# oshpark2_1_2-peripherals.net
KiCad netlist of a schematic drawn in EAGLE
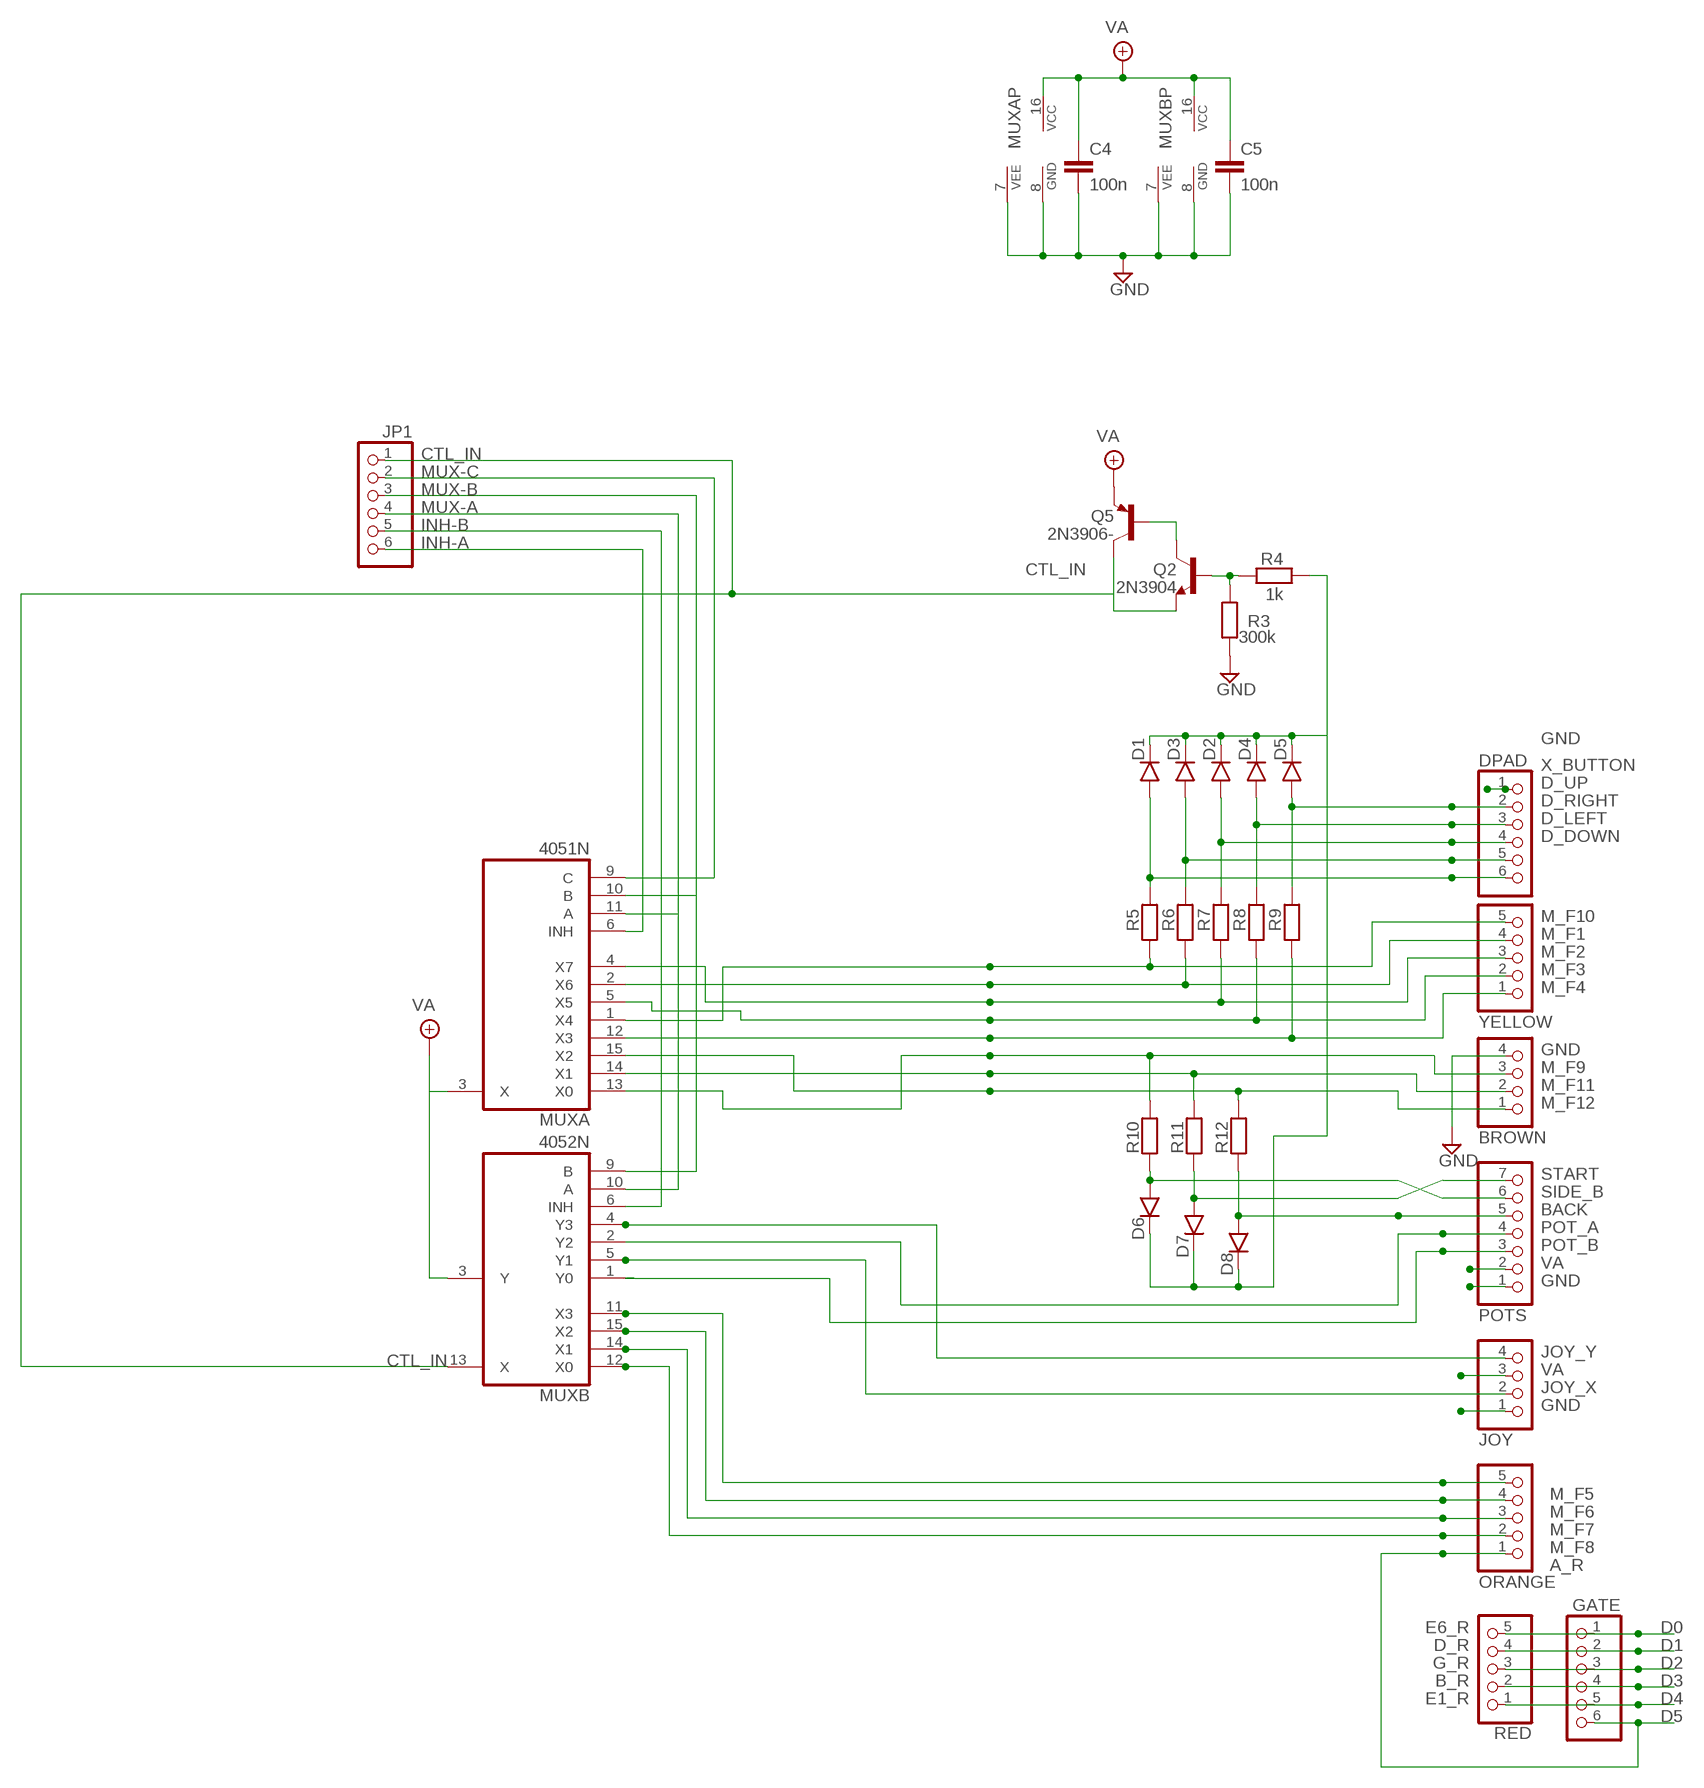
[diagram p0: schematic, sheet 1]

(export (version "E")
  (design (tool "Eeschema 10.0.6"))
  (components
    (comp (ref "BROWN")
      (value "PINHD-1X4")
      (footprint "eagle-import:1X04")
      (libsource (lib "eagle-import") (part "PINHD-1X4"))
    )
    (comp (ref "C4")
      (value "100n")
      (footprint "eagle-import:050X030_050_1")
      (libsource (lib "eagle-import") (part "050X030_0501"))
    )
    (comp (ref "C5")
      (value "100n")
      (footprint "eagle-import:050X030_050_3")
      (libsource (lib "eagle-import") (part "050X030_050"))
    )
    (comp (ref "D1")
      (value "1N4148-2")
      (footprint "eagle-import:DO35-2")
      (libsource (lib "eagle-import") (part "1N4148-2"))
    )
    (comp (ref "D2")
      (value "1N4148-2")
      (footprint "eagle-import:DO35-2")
      (libsource (lib "eagle-import") (part "1N4148-2"))
    )
    (comp (ref "D3")
      (value "1N4148-2")
      (footprint "eagle-import:DO35-2")
      (libsource (lib "eagle-import") (part "1N4148-2"))
    )
    (comp (ref "D4")
      (value "1N4148-2")
      (footprint "eagle-import:DO35-2")
      (libsource (lib "eagle-import") (part "1N4148-2"))
    )
    (comp (ref "D5")
      (value "1N4148-2")
      (footprint "eagle-import:DO35-2")
      (libsource (lib "eagle-import") (part "1N4148-2"))
    )
    (comp (ref "D6")
      (value "1N4148-2")
      (footprint "eagle-import:DO35-2")
      (libsource (lib "eagle-import") (part "1N4148-2"))
    )
    (comp (ref "D7")
      (value "1N4148-2")
      (footprint "eagle-import:DO35-2")
      (libsource (lib "eagle-import") (part "1N4148-2"))
    )
    (comp (ref "D8")
      (value "1N4148-2")
      (footprint "eagle-import:DO35-2")
      (libsource (lib "eagle-import") (part "1N4148-2"))
    )
    (comp (ref "DPAD")
      (value "PINHD-1X6")
      (footprint "eagle-import:1X06")
      (libsource (lib "eagle-import") (part "PINHD-1X6"))
    )
    (comp (ref "GATE")
      (value "PINHD-1X6")
      (footprint "eagle-import:1X06")
      (libsource (lib "eagle-import") (part "PINHD-1X6"))
    )
    (comp (ref "JOY")
      (value "PINHD-1X4")
      (footprint "eagle-import:1X04")
      (libsource (lib "eagle-import") (part "PINHD-1X4"))
    )
    (comp (ref "JP1")
      (value "PINHD-1X6")
      (footprint "eagle-import:1X06")
      (libsource (lib "eagle-import") (part "PINHD-1X6"))
    )
    (comp (ref "MUXA")
      (value "4051N")
      (footprint "eagle-import:DIL16")
      (libsource (lib "eagle-import") (part "4051N"))
    )
    (comp (ref "MUXB")
      (value "4052N")
      (footprint "eagle-import:DIL16")
      (libsource (lib "eagle-import") (part "4052N"))
    )
    (comp (ref "ORANGE")
      (value "PINHD-1X5")
      (footprint "eagle-import:1X05")
      (libsource (lib "eagle-import") (part "PINHD-1X5"))
    )
    (comp (ref "POTS")
      (value "PINHD-1X7")
      (footprint "eagle-import:1X07")
      (libsource (lib "eagle-import") (part "PINHD-1X7"))
    )
    (comp (ref "Q2")
      (value "2N3904")
      (footprint "eagle-import:TO92-")
      (libsource (lib "eagle-import") (part "2N3904"))
    )
    (comp (ref "Q5")
      (value "2N3906-")
      (footprint "eagle-import:TO92-")
      (libsource (lib "eagle-import") (part "2N3906-"))
    )
    (comp (ref "R3")
      (value "300k")
      (footprint "eagle-import:R0207_1V")
      (libsource (lib "eagle-import") (part "6MM-EU1"))
    )
    (comp (ref "R4")
      (value "1k")
      (footprint "eagle-import:R0207_3")
      (libsource (lib "eagle-import") (part "6MM-EU"))
    )
    (comp (ref "R5")
      (value "30k")
      (footprint "eagle-import:R0207_1V")
      (libsource (lib "eagle-import") (part "6MM-EU1"))
    )
    (comp (ref "R6")
      (value "30k")
      (footprint "eagle-import:R0207_1V")
      (libsource (lib "eagle-import") (part "6MM-EU1"))
    )
    (comp (ref "R7")
      (value "30k")
      (footprint "eagle-import:R0207_1V")
      (libsource (lib "eagle-import") (part "6MM-EU1"))
    )
    (comp (ref "R8")
      (value "30k")
      (footprint "eagle-import:R0207_1V")
      (libsource (lib "eagle-import") (part "6MM-EU1"))
    )
    (comp (ref "R9")
      (value "30k")
      (footprint "eagle-import:R0207_1V")
      (libsource (lib "eagle-import") (part "6MM-EU1"))
    )
    (comp (ref "R10")
      (value "30k")
      (footprint "eagle-import:R0207_2V")
      (libsource (lib "eagle-import") (part "6MM-EU2"))
    )
    (comp (ref "R11")
      (value "30k")
      (footprint "eagle-import:R0207_2V")
      (libsource (lib "eagle-import") (part "6MM-EU2"))
    )
    (comp (ref "R12")
      (value "30k")
      (footprint "eagle-import:R0207_2V")
      (libsource (lib "eagle-import") (part "6MM-EU2"))
    )
    (comp (ref "RED")
      (value "PINHD-1X5")
      (footprint "eagle-import:1X05")
      (libsource (lib "eagle-import") (part "PINHD-1X5"))
    )
    (comp (ref "YELLOW")
      (value "PINHD-1X5")
      (footprint "eagle-import:1X05")
      (libsource (lib "eagle-import") (part "PINHD-1X5"))
    )
  )
  (nets
    (net (code "1") (name "/BACK") (class "Default")
      (node (ref "D7") (pin "A") (pinfunction "A_A") (pintype "passive"))
      (node (ref "POTS") (pin "7") (pinfunction "7_7") (pintype "passive"))
      (node (ref "R11") (pin "2") (pinfunction "2_2") (pintype "passive"))
    )
    (net (code "2") (name "/CTL_IN") (class "Default")
      (node (ref "JP1") (pin "1") (pinfunction "1_1") (pintype "passive"))
      (node (ref "MUXB") (pin "13") (pinfunction "X_13") (pintype "bidirectional"))
      (node (ref "Q2") (pin "3") (pinfunction "E_3") (pintype "passive"))
      (node (ref "Q5") (pin "1") (pinfunction "C_1") (pintype "passive"))
    )
    (net (code "3") (name "/D0") (class "Default")
      (node (ref "GATE") (pin "1") (pinfunction "1_1") (pintype "passive"))
      (node (ref "RED") (pin "5") (pinfunction "5_5") (pintype "passive"))
    )
    (net (code "4") (name "/D1") (class "Default")
      (node (ref "GATE") (pin "2") (pinfunction "2_2") (pintype "passive"))
      (node (ref "RED") (pin "4") (pinfunction "4_4") (pintype "passive"))
    )
    (net (code "5") (name "/D2") (class "Default")
      (node (ref "GATE") (pin "3") (pinfunction "3_3") (pintype "passive"))
      (node (ref "RED") (pin "3") (pinfunction "3_3") (pintype "passive"))
    )
    (net (code "6") (name "/D3") (class "Default")
      (node (ref "GATE") (pin "4") (pinfunction "4_4") (pintype "passive"))
      (node (ref "RED") (pin "2") (pinfunction "2_2") (pintype "passive"))
    )
    (net (code "7") (name "/D4") (class "Default")
      (node (ref "GATE") (pin "5") (pinfunction "5_5") (pintype "passive"))
      (node (ref "RED") (pin "1") (pinfunction "1_1") (pintype "passive"))
    )
    (net (code "8") (name "/D5") (class "Default")
      (node (ref "GATE") (pin "6") (pinfunction "6_6") (pintype "passive"))
      (node (ref "ORANGE") (pin "1") (pinfunction "1_1") (pintype "passive"))
    )
    (net (code "9") (name "/D_DOWN") (class "Default")
      (node (ref "D1") (pin "A") (pinfunction "A_A") (pintype "passive"))
      (node (ref "DPAD") (pin "6") (pinfunction "6_6") (pintype "passive"))
      (node (ref "R5") (pin "2") (pinfunction "2_2") (pintype "passive"))
    )
    (net (code "10") (name "/D_LEFT") (class "Default")
      (node (ref "D3") (pin "A") (pinfunction "A_A") (pintype "passive"))
      (node (ref "DPAD") (pin "5") (pinfunction "5_5") (pintype "passive"))
      (node (ref "R6") (pin "2") (pinfunction "2_2") (pintype "passive"))
    )
    (net (code "11") (name "/D_RIGHT") (class "Default")
      (node (ref "D2") (pin "A") (pinfunction "A_A") (pintype "passive"))
      (node (ref "DPAD") (pin "4") (pinfunction "4_4") (pintype "passive"))
      (node (ref "R7") (pin "2") (pinfunction "2_2") (pintype "passive"))
    )
    (net (code "12") (name "/D_UP") (class "Default")
      (node (ref "D4") (pin "A") (pinfunction "A_A") (pintype "passive"))
      (node (ref "DPAD") (pin "3") (pinfunction "3_3") (pintype "passive"))
      (node (ref "R8") (pin "2") (pinfunction "2_2") (pintype "passive"))
    )
    (net (code "13") (name "/INH-A") (class "Default")
      (node (ref "JP1") (pin "6") (pinfunction "6_6") (pintype "passive"))
      (node (ref "MUXA") (pin "6") (pinfunction "INH_6") (pintype "input"))
    )
    (net (code "14") (name "/INH-B") (class "Default")
      (node (ref "JP1") (pin "5") (pinfunction "5_5") (pintype "passive"))
      (node (ref "MUXB") (pin "6") (pinfunction "INH_6") (pintype "input"))
    )
    (net (code "15") (name "/JOY_X") (class "Default")
      (node (ref "JOY") (pin "2") (pinfunction "2_2") (pintype "passive"))
      (node (ref "MUXB") (pin "5") (pinfunction "Y1_5") (pintype "bidirectional"))
    )
    (net (code "16") (name "/JOY_Y") (class "Default")
      (node (ref "JOY") (pin "4") (pinfunction "4_4") (pintype "passive"))
      (node (ref "MUXB") (pin "4") (pinfunction "Y3_4") (pintype "bidirectional"))
    )
    (net (code "17") (name "/MUX-A") (class "Default")
      (node (ref "JP1") (pin "4") (pinfunction "4_4") (pintype "passive"))
      (node (ref "MUXA") (pin "11") (pinfunction "A_11") (pintype "input"))
      (node (ref "MUXB") (pin "10") (pinfunction "A_10") (pintype "input"))
    )
    (net (code "18") (name "/MUX-B") (class "Default")
      (node (ref "JP1") (pin "3") (pinfunction "3_3") (pintype "passive"))
      (node (ref "MUXA") (pin "10") (pinfunction "B_10") (pintype "input"))
      (node (ref "MUXB") (pin "9") (pinfunction "B_9") (pintype "input"))
    )
    (net (code "19") (name "/MUX-C") (class "Default")
      (node (ref "JP1") (pin "2") (pinfunction "2_2") (pintype "passive"))
      (node (ref "MUXA") (pin "9") (pinfunction "C_9") (pintype "input"))
    )
    (net (code "20") (name "/M_F1") (class "Default")
      (node (ref "MUXA") (pin "2") (pinfunction "X6_2") (pintype "bidirectional"))
      (node (ref "R6") (pin "1") (pinfunction "1_1") (pintype "passive"))
      (node (ref "YELLOW") (pin "4") (pinfunction "4_4") (pintype "passive"))
    )
    (net (code "21") (name "/M_F2") (class "Default")
      (node (ref "MUXA") (pin "4") (pinfunction "X7_4") (pintype "bidirectional"))
      (node (ref "R7") (pin "1") (pinfunction "1_1") (pintype "passive"))
      (node (ref "YELLOW") (pin "3") (pinfunction "3_3") (pintype "passive"))
    )
    (net (code "22") (name "/M_F3") (class "Default")
      (node (ref "MUXA") (pin "5") (pinfunction "X5_5") (pintype "bidirectional"))
      (node (ref "R8") (pin "1") (pinfunction "1_1") (pintype "passive"))
      (node (ref "YELLOW") (pin "2") (pinfunction "2_2") (pintype "passive"))
    )
    (net (code "23") (name "/M_F4") (class "Default")
      (node (ref "MUXA") (pin "12") (pinfunction "X3_12") (pintype "bidirectional"))
      (node (ref "R9") (pin "1") (pinfunction "1_1") (pintype "passive"))
      (node (ref "YELLOW") (pin "1") (pinfunction "1_1") (pintype "passive"))
    )
    (net (code "24") (name "/M_F5") (class "Default")
      (node (ref "MUXB") (pin "11") (pinfunction "X3_11") (pintype "bidirectional"))
      (node (ref "ORANGE") (pin "5") (pinfunction "5_5") (pintype "passive"))
    )
    (net (code "25") (name "/M_F6") (class "Default")
      (node (ref "MUXB") (pin "15") (pinfunction "X2_15") (pintype "bidirectional"))
      (node (ref "ORANGE") (pin "4") (pinfunction "4_4") (pintype "passive"))
    )
    (net (code "26") (name "/M_F7") (class "Default")
      (node (ref "MUXB") (pin "14") (pinfunction "X1_14") (pintype "bidirectional"))
      (node (ref "ORANGE") (pin "3") (pinfunction "3_3") (pintype "passive"))
    )
    (net (code "27") (name "/M_F8") (class "Default")
      (node (ref "MUXB") (pin "12") (pinfunction "X0_12") (pintype "bidirectional"))
      (node (ref "ORANGE") (pin "2") (pinfunction "2_2") (pintype "passive"))
    )
    (net (code "28") (name "/M_F9") (class "Default")
      (node (ref "BROWN") (pin "3") (pinfunction "3_3") (pintype "passive"))
      (node (ref "MUXA") (pin "13") (pinfunction "X0_13") (pintype "bidirectional"))
      (node (ref "R10") (pin "1") (pinfunction "1_1") (pintype "passive"))
    )
    (net (code "29") (name "/M_F10") (class "Default")
      (node (ref "MUXA") (pin "1") (pinfunction "X4_1") (pintype "bidirectional"))
      (node (ref "R5") (pin "1") (pinfunction "1_1") (pintype "passive"))
      (node (ref "YELLOW") (pin "5") (pinfunction "5_5") (pintype "passive"))
    )
    (net (code "30") (name "/M_F11") (class "Default")
      (node (ref "BROWN") (pin "2") (pinfunction "2_2") (pintype "passive"))
      (node (ref "MUXA") (pin "14") (pinfunction "X1_14") (pintype "bidirectional"))
      (node (ref "R11") (pin "1") (pinfunction "1_1") (pintype "passive"))
    )
    (net (code "31") (name "/M_F12") (class "Default")
      (node (ref "BROWN") (pin "1") (pinfunction "1_1") (pintype "passive"))
      (node (ref "MUXA") (pin "15") (pinfunction "X2_15") (pintype "bidirectional"))
      (node (ref "R12") (pin "1") (pinfunction "1_1") (pintype "passive"))
    )
    (net (code "32") (name "/POT_A") (class "Default")
      (node (ref "MUXB") (pin "2") (pinfunction "Y2_2") (pintype "bidirectional"))
      (node (ref "POTS") (pin "4") (pinfunction "4_4") (pintype "passive"))
    )
    (net (code "33") (name "/POT_B") (class "Default")
      (node (ref "MUXB") (pin "1") (pinfunction "Y0_1") (pintype "bidirectional"))
      (node (ref "POTS") (pin "3") (pinfunction "3_3") (pintype "passive"))
    )
    (net (code "34") (name "/SIDE_B") (class "Default")
      (node (ref "D6") (pin "A") (pinfunction "A_A") (pintype "passive"))
      (node (ref "POTS") (pin "6") (pinfunction "6_6") (pintype "passive"))
      (node (ref "R10") (pin "2") (pinfunction "2_2") (pintype "passive"))
    )
    (net (code "35") (name "/START") (class "Default")
      (node (ref "D8") (pin "A") (pinfunction "A_A") (pintype "passive"))
      (node (ref "POTS") (pin "5") (pinfunction "5_5") (pintype "passive"))
      (node (ref "R12") (pin "2") (pinfunction "2_2") (pintype "passive"))
    )
    (net (code "36") (name "/X_BUTTON") (class "Default")
      (node (ref "D5") (pin "A") (pinfunction "A_A") (pintype "passive"))
      (node (ref "DPAD") (pin "2") (pinfunction "2_2") (pintype "passive"))
      (node (ref "R9") (pin "2") (pinfunction "2_2") (pintype "passive"))
    )
    (net (code "37") (name "GND") (class "Default")
      (node (ref "BROWN") (pin "4") (pinfunction "4_4") (pintype "passive"))
      (node (ref "C4") (pin "2") (pinfunction "2_2") (pintype "passive"))
      (node (ref "C5") (pin "2") (pinfunction "2_2") (pintype "passive"))
      (node (ref "DPAD") (pin "1") (pinfunction "1_1") (pintype "passive"))
      (node (ref "JOY") (pin "1") (pinfunction "1_1") (pintype "passive"))
      (node (ref "MUXA") (pin "7") (pinfunction "VEE_7") (pintype "power_in"))
      (node (ref "MUXA") (pin "8") (pinfunction "GND_8") (pintype "power_in"))
      (node (ref "MUXB") (pin "7") (pinfunction "VEE_7") (pintype "power_in"))
      (node (ref "MUXB") (pin "8") (pinfunction "GND_8") (pintype "power_in"))
      (node (ref "POTS") (pin "1") (pinfunction "1_1") (pintype "passive"))
      (node (ref "R3") (pin "2") (pinfunction "2_2") (pintype "passive"))
    )
    (net (code "38") (name "Net-(D1-PadC)") (class "Default")
      (node (ref "D1") (pin "C") (pinfunction "C_C") (pintype "passive"))
      (node (ref "D2") (pin "C") (pinfunction "C_C") (pintype "passive"))
      (node (ref "D3") (pin "C") (pinfunction "C_C") (pintype "passive"))
      (node (ref "D4") (pin "C") (pinfunction "C_C") (pintype "passive"))
      (node (ref "D5") (pin "C") (pinfunction "C_C") (pintype "passive"))
      (node (ref "D6") (pin "C") (pinfunction "C_C") (pintype "passive"))
      (node (ref "D7") (pin "C") (pinfunction "C_C") (pintype "passive"))
      (node (ref "D8") (pin "C") (pinfunction "C_C") (pintype "passive"))
      (node (ref "R4") (pin "1") (pinfunction "1_1") (pintype "passive"))
    )
    (net (code "39") (name "Net-(Q2-B)") (class "Default")
      (node (ref "Q2") (pin "2") (pinfunction "B_2") (pintype "passive"))
      (node (ref "R3") (pin "1") (pinfunction "1_1") (pintype "passive"))
      (node (ref "R4") (pin "2") (pinfunction "2_2") (pintype "passive"))
    )
    (net (code "40") (name "Net-(Q2-C)") (class "Default")
      (node (ref "Q2") (pin "1") (pinfunction "C_1") (pintype "passive"))
      (node (ref "Q5") (pin "2") (pinfunction "B_2") (pintype "passive"))
    )
    (net (code "41") (name "VA") (class "Default")
      (node (ref "C4") (pin "1") (pinfunction "1_1") (pintype "passive"))
      (node (ref "C5") (pin "1") (pinfunction "1_1") (pintype "passive"))
      (node (ref "JOY") (pin "3") (pinfunction "3_3") (pintype "passive"))
      (node (ref "MUXA") (pin "16") (pinfunction "VCC_16") (pintype "power_in"))
      (node (ref "MUXA") (pin "3") (pinfunction "X_3") (pintype "bidirectional"))
      (node (ref "MUXB") (pin "16") (pinfunction "VCC_16") (pintype "power_in"))
      (node (ref "MUXB") (pin "3") (pinfunction "Y_3") (pintype "bidirectional"))
      (node (ref "POTS") (pin "2") (pinfunction "2_2") (pintype "passive"))
      (node (ref "Q5") (pin "3") (pinfunction "E_3") (pintype "passive"))
    )
  )
)
